# design.net
KiCad netlist of a schematic drawn in Altium Designer
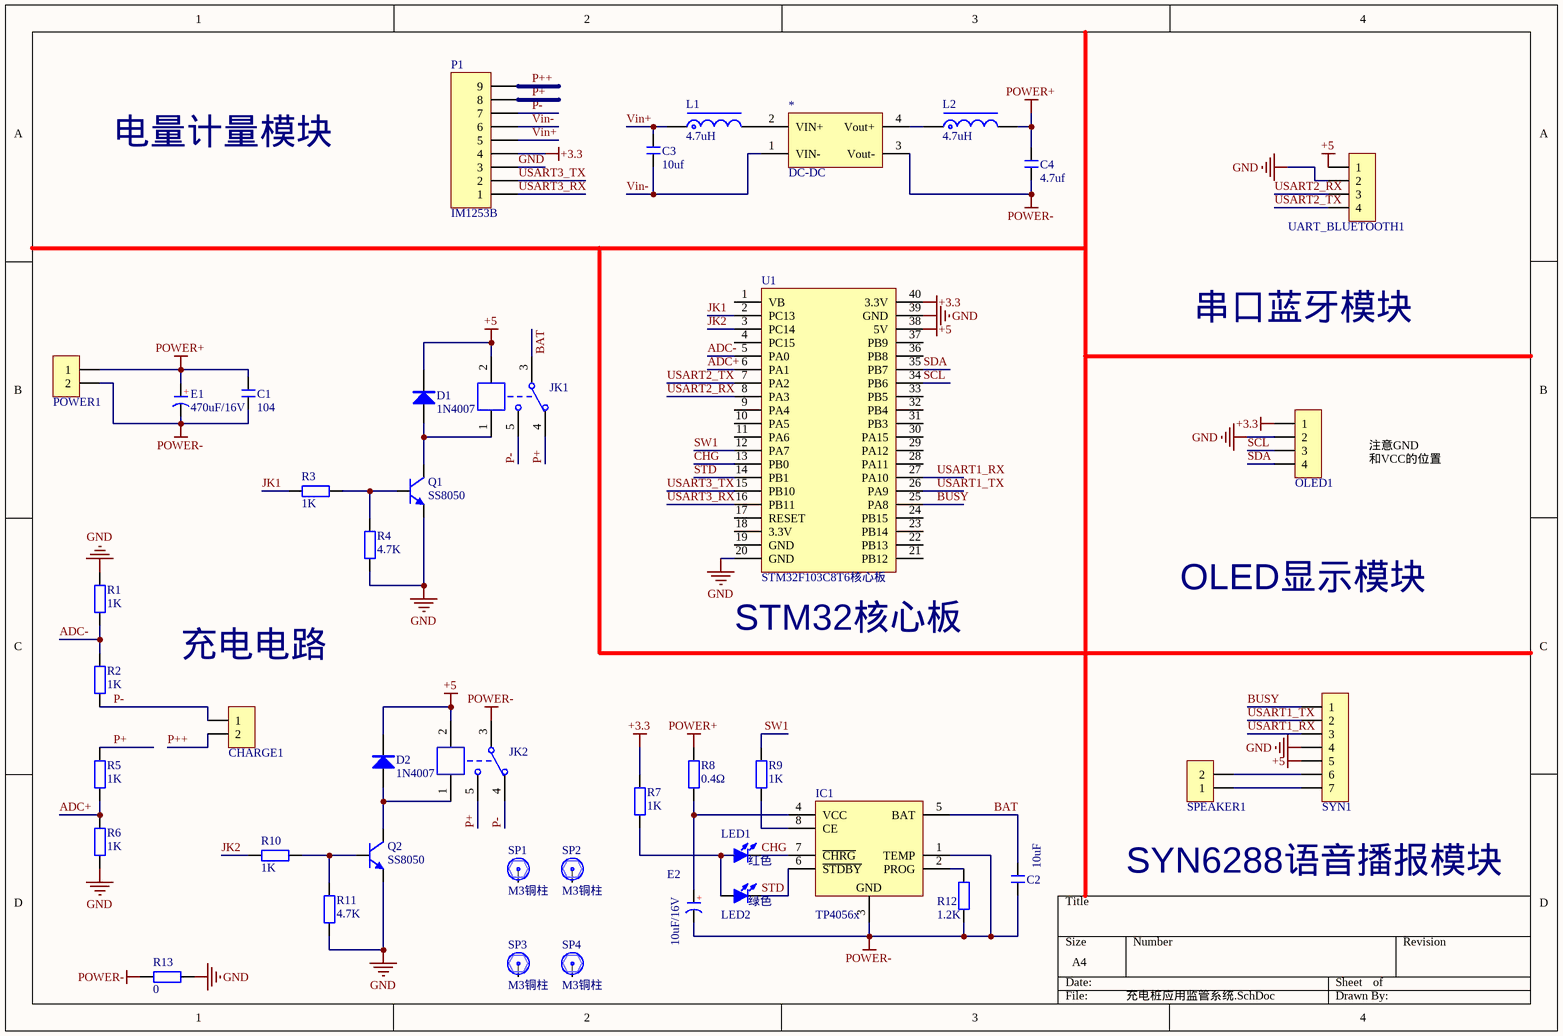
[diagram p0: 充电桩应用监管系统.SchDoc]

(export (version "E")
  (design (tool "Eeschema 10.0.6"))
  (components
    (comp (ref "*") (value "DC-DC") (libsource (lib "HLK-1D0505A") (part "Component_1")))
    (comp (ref "C1")
      (value "104")
      (footprint "R 0805_M")
      (description "直插瓷片电容")
      (fields (field (name "版权归属") "源创客"))
      (libsource (lib "3.1   - 电阻-电容-电感") (part "C-CC"))
    )
    (comp (ref "C2")
      (value "10uF")
      (footprint "C 1206_M")
      (description "无极性贴片电容")
      (fields (field (name "版权归属") "源创客"))
      (libsource (lib "3.1   - 电阻-电容-电感") (part "C"))
    )
    (comp (ref "C3")
      (value "10uf")
      (footprint "R 0805_M")
      (description "直插瓷片电容")
      (fields (field (name "版权归属") "源创客"))
      (libsource (lib "3.1   - 电阻-电容-电感") (part "C-CC"))
    )
    (comp (ref "C4")
      (value "4.7uf")
      (footprint "R 0805_M")
      (description "直插瓷片电容")
      (fields (field (name "版权归属") "源创客"))
      (libsource (lib "3.1   - 电阻-电容-电感") (part "C-CC"))
    )
    (comp (ref "CHARGE1")
      (value "HDR-1X2")
      (footprint "KF301-5.0-2P")
      (description "2P接插件")
      (fields (field (name "版权归属") "源创客"))
      (libsource (lib "") (part "Header 2_2"))
    )
    (comp (ref "D1")
      (value "1N4007")
      (footprint "DO-41")
      (description "整流二极管")
      (fields (field (name "版权归属") "源创客"))
      (libsource (lib "8.1   - 二极管-整流桥") (part "1N4007"))
    )
    (comp (ref "D2")
      (value "1N4007")
      (footprint "DO-41")
      (description "整流二极管")
      (fields (field (name "版权归属") "源创客"))
      (libsource (lib "8.1   - 二极管-整流桥") (part "1N4007"))
    )
    (comp (ref "E1")
      (value "470uF/16V")
      (footprint "CAP 2.0*5*11 - BK")
      (description "直插电解电容")
      (fields (field (name "版权归属") "源创客"))
      (libsource (lib "3.1   - 电阻-电容-电感") (part "C-CAP"))
    )
    (comp (ref "E2")
      (value "10uF/16V")
      (footprint "CAP 2.0*5*11 - BK")
      (description "直插电解电容")
      (fields (field (name "版权归属") "源创客"))
      (libsource (lib "3.1   - 电阻-电容-电感") (part "C-CAP"))
    )
    (comp (ref "IC1")
      (value "TP4056x")
      (footprint "ESOP8_M")
      (description "锂电池充电管理")
      (fields (field (name "版权归属") "源创客"))
      (libsource (lib "1.3   - 电源类芯片") (part "TP4056"))
    )
    (comp (ref "JK1")
      (value "~")
      (footprint "SRD-C_B")
      (description "5V一组转换")
      (fields (field (name "版权归属") "源创客"))
      (libsource (lib "7.1   - 继电器") (part "SRD-05VDC-SL-C"))
    )
    (comp (ref "JK2")
      (value "~")
      (footprint "SRD-C_B")
      (description "5V一组转换")
      (fields (field (name "版权归属") "源创客"))
      (libsource (lib "7.1   - 继电器") (part "SRD-05VDC-SL-C"))
    )
    (comp (ref "L1")
      (value "4.7uH")
      (footprint "NR2520")
      (description "NR磁胶电感")
      (fields (field (name "版权归属") "源创客"))
      (libsource (lib "3.1   - 电阻-电容-电感") (part "L-NR"))
    )
    (comp (ref "L2")
      (value "4.7uH")
      (footprint "NR2520")
      (description "NR磁胶电感")
      (fields (field (name "版权归属") "源创客"))
      (libsource (lib "3.1   - 电阻-电容-电感") (part "L-NR"))
    )
    (comp (ref "LED1")
      (value "红色")
      (footprint "LED 0805R")
      (description "插件LED")
      (fields (field (name "版权归属") "源创客"))
      (libsource (lib "9.1   - LED") (part "LED-3MM"))
    )
    (comp (ref "LED2")
      (value "绿色")
      (footprint "LED 0805G")
      (description "插件LED")
      (fields (field (name "版权归属") "源创客"))
      (libsource (lib "9.1   - LED") (part "LED-3MM"))
    )
    (comp (ref "OLED1")
      (value "HDR-1X4")
      (footprint "HDR2.54-M-LI-4P")
      (description "4P接插件")
      (fields (field (name "版权归属") "源创客"))
      (libsource (lib "4.5   - 接插件-脚距2.54") (part "Header 4"))
    )
    (comp (ref "P1")
      (value "IM1253B")
      (footprint "HDR1X9")
      (description "Header, 9-Pin")
      (fields (field (name "PUBLISHER") "Altium Limited"))
      (libsource (lib "Miscellaneous Connectors") (part "Header 9"))
    )
    (comp (ref "POWER1")
      (value "HDR-1X2")
      (footprint "KF301-5.0-2P")
      (description "2P接插件")
      (fields (field (name "版权归属") "源创客"))
      (libsource (lib "") (part "Header 2_1"))
    )
    (comp (ref "Q1")
      (value "SS8050")
      (footprint "TO92A")
      (description "高频放大-NPN型")
      (fields (field (name "版权归属") "源创客"))
      (libsource (lib "6.2   - 三极管") (part "8050-DIP"))
    )
    (comp (ref "Q2")
      (value "SS8050")
      (footprint "TO92A")
      (description "高频放大-NPN型")
      (fields (field (name "版权归属") "源创客"))
      (libsource (lib "6.2   - 三极管") (part "8050-DIP"))
    )
    (comp (ref "R1")
      (value "1K")
      (footprint "R 0805_M")
      (description "直插色环电阻")
      (fields (field (name "版权归属") "源创客"))
      (libsource (lib "3.1   - 电阻-电容-电感") (part "R-CRR"))
    )
    (comp (ref "R2")
      (value "1K")
      (footprint "R 0805_M")
      (description "直插色环电阻")
      (fields (field (name "版权归属") "源创客"))
      (libsource (lib "3.1   - 电阻-电容-电感") (part "R-CRR"))
    )
    (comp (ref "R3")
      (value "1K")
      (footprint "R 0805_M")
      (description "直插色环电阻")
      (fields (field (name "版权归属") "源创客"))
      (libsource (lib "3.1   - 电阻-电容-电感") (part "R-CRR"))
    )
    (comp (ref "R4")
      (value "4.7K")
      (footprint "R 0805_M")
      (description "直插色环电阻")
      (fields (field (name "版权归属") "源创客"))
      (libsource (lib "3.1   - 电阻-电容-电感") (part "R-CRR"))
    )
    (comp (ref "R5")
      (value "1K")
      (footprint "R 0805_M")
      (description "直插色环电阻")
      (fields (field (name "版权归属") "源创客"))
      (libsource (lib "3.1   - 电阻-电容-电感") (part "R-CRR"))
    )
    (comp (ref "R6")
      (value "1K")
      (footprint "R 0805_M")
      (description "直插色环电阻")
      (fields (field (name "版权归属") "源创客"))
      (libsource (lib "3.1   - 电阻-电容-电感") (part "R-CRR"))
    )
    (comp (ref "R7")
      (value "1K")
      (footprint "R 0805_M")
      (description "直插色环电阻")
      (fields (field (name "版权归属") "源创客"))
      (libsource (lib "3.1   - 电阻-电容-电感") (part "R-CRR"))
    )
    (comp (ref "R8")
      (value "0.4Ω")
      (footprint "R 0805_M")
      (description "直插色环电阻")
      (fields (field (name "版权归属") "源创客"))
      (libsource (lib "3.1   - 电阻-电容-电感") (part "R-CRR"))
    )
    (comp (ref "R9")
      (value "1K")
      (footprint "R 0805_M")
      (description "直插色环电阻")
      (fields (field (name "版权归属") "源创客"))
      (libsource (lib "3.1   - 电阻-电容-电感") (part "R-CRR"))
    )
    (comp (ref "R10")
      (value "1K")
      (footprint "R 0805_M")
      (description "直插色环电阻")
      (fields (field (name "版权归属") "源创客"))
      (libsource (lib "3.1   - 电阻-电容-电感") (part "R-CRR"))
    )
    (comp (ref "R11")
      (value "4.7K")
      (footprint "R 0805_M")
      (description "直插色环电阻")
      (fields (field (name "版权归属") "源创客"))
      (libsource (lib "3.1   - 电阻-电容-电感") (part "R-CRR"))
    )
    (comp (ref "R12")
      (value "1.2K")
      (footprint "R 0805_M")
      (description "直插色环电阻")
      (fields (field (name "版权归属") "源创客"))
      (libsource (lib "3.1   - 电阻-电容-电感") (part "R-CRR"))
    )
    (comp (ref "R13")
      (value "0")
      (footprint "R 0805_M")
      (description "直插色环电阻")
      (fields (field (name "版权归属") "源创客"))
      (libsource (lib "3.1   - 电阻-电容-电感") (part "R-CRR"))
    )
    (comp (ref "SP1")
      (value "M3铜柱")
      (footprint "M3x4_L")
      (description "铜柱")
      (fields (field (name "版权归属") "源创客"))
      (libsource (lib "15.1 - 未分类器件") (part "铜柱小焊盘"))
    )
    (comp (ref "SP2")
      (value "M3铜柱")
      (footprint "M3x4_L")
      (description "铜柱")
      (fields (field (name "版权归属") "源创客"))
      (libsource (lib "15.1 - 未分类器件") (part "铜柱小焊盘"))
    )
    (comp (ref "SP3")
      (value "M3铜柱")
      (footprint "M3x4_L")
      (description "铜柱")
      (fields (field (name "版权归属") "源创客"))
      (libsource (lib "15.1 - 未分类器件") (part "铜柱小焊盘"))
    )
    (comp (ref "SP4")
      (value "M3铜柱")
      (footprint "M3x4_L")
      (description "铜柱")
      (fields (field (name "版权归属") "源创客"))
      (libsource (lib "15.1 - 未分类器件") (part "铜柱小焊盘"))
    )
    (comp (ref "SPEAKER1")
      (value "HDR-1X2")
      (footprint "KF301-5.0-2P")
      (description "2P接插件")
      (fields (field (name "版权归属") "源创客"))
      (libsource (lib "4.9   - 接插件-脚距5.0") (part "Header 2"))
    )
    (comp (ref "SYN1")
      (value "HDR-1X7")
      (footprint "PH2.0-LI-7P")
      (description "7P接插件")
      (fields (field (name "版权归属") "源创客"))
      (libsource (lib "4.4   - 接插件-脚距2.0") (part "Header 7"))
    )
    (comp (ref "U1")
      (value "STM32F103C8T6核心板")
      (footprint "DIP40-600_MH")
      (libsource (lib "STM32F103C8T6核心板") (part "STM32F103C8T6核心板"))
    )
    (comp (ref "UART_BLUETOOTH1")
      (value "HDR-1X4")
      (footprint "HDR2.54-M-LI-4P")
      (description "4P接插件")
      (fields (field (name "版权归属") "源创客"))
      (libsource (lib "4.5   - 接插件-脚距2.54") (part "Header 4"))
    )
  )
  (nets
    (net (code "1") (name "+3.3") (class "Default")
      (node (ref "OLED1") (pin "1") (pinfunction "1_1") (pintype "passive"))
      (node (ref "P1") (pin "4") (pinfunction "4_4") (pintype "passive"))
      (node (ref "R7") (pin "2") (pinfunction "2_2") (pintype "passive"))
      (node (ref "U1") (pin "40") (pinfunction "3.3V_40") (pintype "passive"))
    )
    (net (code "2") (name "+5") (class "Default")
      (node (ref "D1") (pin "2") (pinfunction "K_2") (pintype "passive"))
      (node (ref "D2") (pin "2") (pinfunction "K_2") (pintype "passive"))
      (node (ref "JK1") (pin "2") (pinfunction "2_2") (pintype "passive"))
      (node (ref "JK2") (pin "2") (pinfunction "2_2") (pintype "passive"))
      (node (ref "SYN1") (pin "5") (pinfunction "5_5") (pintype "passive"))
      (node (ref "U1") (pin "38") (pinfunction "5V_38") (pintype "passive"))
      (node (ref "UART_BLUETOOTH1") (pin "1") (pinfunction "1_1") (pintype "passive"))
    )
    (net (code "3") (name "/ADC+") (class "Default")
      (node (ref "R5") (pin "1") (pinfunction "1_1") (pintype "passive"))
      (node (ref "R6") (pin "2") (pinfunction "2_2") (pintype "passive"))
      (node (ref "U1") (pin "6") (pinfunction "PA1_6") (pintype "passive"))
    )
    (net (code "4") (name "/ADC-") (class "Default")
      (node (ref "R1") (pin "1") (pinfunction "1_1") (pintype "passive"))
      (node (ref "R2") (pin "2") (pinfunction "2_2") (pintype "passive"))
      (node (ref "U1") (pin "5") (pinfunction "PA0_5") (pintype "passive"))
    )
    (net (code "5") (name "/BAT") (class "Default")
      (node (ref "C2") (pin "2") (pinfunction "2_2") (pintype "passive"))
      (node (ref "IC1") (pin "5") (pinfunction "BAT_5") (pintype "passive"))
      (node (ref "JK1") (pin "3") (pinfunction "3_3") (pintype "passive"))
    )
    (net (code "6") (name "/BUSY") (class "Default")
      (node (ref "SYN1") (pin "1") (pinfunction "1_1") (pintype "passive"))
      (node (ref "U1") (pin "25") (pinfunction "PA8_25") (pintype "passive"))
    )
    (net (code "7") (name "/CHG") (class "Default")
      (node (ref "IC1") (pin "7") (pinfunction "~{CHRG}_7") (pintype "passive"))
      (node (ref "LED1") (pin "2") (pinfunction "K_2") (pintype "passive"))
      (node (ref "U1") (pin "13") (pinfunction "PB0_13") (pintype "passive"))
    )
    (net (code "8") (name "/JK1") (class "Default")
      (node (ref "R3") (pin "1") (pinfunction "1_1") (pintype "passive"))
      (node (ref "U1") (pin "2") (pinfunction "PC13_2") (pintype "passive"))
    )
    (net (code "9") (name "/JK2") (class "Default")
      (node (ref "R10") (pin "1") (pinfunction "1_1") (pintype "passive"))
      (node (ref "U1") (pin "3") (pinfunction "PC14_3") (pintype "passive"))
    )
    (net (code "10") (name "/P+") (class "Default")
      (node (ref "JK1") (pin "4") (pinfunction "4_4") (pintype "passive"))
      (node (ref "JK2") (pin "5") (pinfunction "5_5") (pintype "passive"))
      (node (ref "P1") (pin "8") (pinfunction "8_8") (pintype "passive"))
      (node (ref "R5") (pin "2") (pinfunction "2_2") (pintype "passive"))
    )
    (net (code "11") (name "/P++") (class "Default")
      (node (ref "CHARGE1") (pin "2") (pinfunction "2_2") (pintype "passive"))
      (node (ref "P1") (pin "9") (pinfunction "9_9") (pintype "passive"))
    )
    (net (code "12") (name "/P-") (class "Default")
      (node (ref "CHARGE1") (pin "1") (pinfunction "1_1") (pintype "passive"))
      (node (ref "JK1") (pin "5") (pinfunction "5_5") (pintype "passive"))
      (node (ref "JK2") (pin "4") (pinfunction "4_4") (pintype "passive"))
      (node (ref "P1") (pin "7") (pinfunction "7_7") (pintype "passive"))
      (node (ref "R2") (pin "1") (pinfunction "1_1") (pintype "passive"))
    )
    (net (code "13") (name "/SCL") (class "Default")
      (node (ref "OLED1") (pin "3") (pinfunction "3_3") (pintype "passive"))
      (node (ref "U1") (pin "34") (pinfunction "PB6_34") (pintype "passive"))
    )
    (net (code "14") (name "/SDA") (class "Default")
      (node (ref "OLED1") (pin "4") (pinfunction "4_4") (pintype "passive"))
      (node (ref "U1") (pin "35") (pinfunction "PB7_35") (pintype "passive"))
    )
    (net (code "15") (name "/STD") (class "Default")
      (node (ref "IC1") (pin "6") (pinfunction "~{STDBY}_6") (pintype "passive"))
      (node (ref "LED2") (pin "2") (pinfunction "K_2") (pintype "passive"))
      (node (ref "U1") (pin "14") (pinfunction "PB1_14") (pintype "passive"))
    )
    (net (code "16") (name "/SW1") (class "Default")
      (node (ref "R9") (pin "1") (pinfunction "1_1") (pintype "passive"))
      (node (ref "U1") (pin "12") (pinfunction "PA7_12") (pintype "passive"))
    )
    (net (code "17") (name "/USART1_RX") (class "Default")
      (node (ref "SYN1") (pin "3") (pinfunction "3_3") (pintype "passive"))
      (node (ref "U1") (pin "27") (pinfunction "PA10_27") (pintype "passive"))
    )
    (net (code "18") (name "/USART1_TX") (class "Default")
      (node (ref "SYN1") (pin "2") (pinfunction "2_2") (pintype "passive"))
      (node (ref "U1") (pin "26") (pinfunction "PA9_26") (pintype "passive"))
    )
    (net (code "19") (name "/USART2_RX") (class "Default")
      (node (ref "U1") (pin "8") (pinfunction "PA3_8") (pintype "passive"))
      (node (ref "UART_BLUETOOTH1") (pin "3") (pinfunction "3_3") (pintype "passive"))
    )
    (net (code "20") (name "/USART2_TX") (class "Default")
      (node (ref "U1") (pin "7") (pinfunction "PA2_7") (pintype "passive"))
      (node (ref "UART_BLUETOOTH1") (pin "4") (pinfunction "4_4") (pintype "passive"))
    )
    (net (code "21") (name "/USART3_RX") (class "Default")
      (node (ref "P1") (pin "1") (pinfunction "1_1") (pintype "passive"))
      (node (ref "U1") (pin "16") (pinfunction "PB11_16") (pintype "passive"))
    )
    (net (code "22") (name "/USART3_TX") (class "Default")
      (node (ref "P1") (pin "2") (pinfunction "2_2") (pintype "passive"))
      (node (ref "U1") (pin "15") (pinfunction "PB10_15") (pintype "passive"))
    )
    (net (code "23") (name "/Vin+") (class "Default")
      (node (ref "C3") (pin "1") (pinfunction "1_1") (pintype "passive"))
      (node (ref "L1") (pin "1") (pinfunction "1_1") (pintype "passive"))
      (node (ref "P1") (pin "5") (pinfunction "5_5") (pintype "passive"))
    )
    (net (code "24") (name "/Vin-") (class "Default")
      (node (ref "*") (pin "1") (pinfunction "VIN-_1") (pintype "passive"))
      (node (ref "C3") (pin "2") (pinfunction "2_2") (pintype "passive"))
      (node (ref "P1") (pin "6") (pinfunction "6_6") (pintype "passive"))
    )
    (net (code "25") (name "GND") (class "Default")
      (node (ref "OLED1") (pin "2") (pinfunction "2_2") (pintype "passive"))
      (node (ref "P1") (pin "3") (pinfunction "3_3") (pintype "passive"))
      (node (ref "Q1") (pin "1") (pinfunction "E_1") (pintype "passive"))
      (node (ref "Q2") (pin "1") (pinfunction "E_1") (pintype "passive"))
      (node (ref "R1") (pin "2") (pinfunction "2_2") (pintype "passive"))
      (node (ref "R11") (pin "1") (pinfunction "1_1") (pintype "passive"))
      (node (ref "R13") (pin "1") (pinfunction "1_1") (pintype "passive"))
      (node (ref "R4") (pin "1") (pinfunction "1_1") (pintype "passive"))
      (node (ref "R6") (pin "1") (pinfunction "1_1") (pintype "passive"))
      (node (ref "SYN1") (pin "4") (pinfunction "4_4") (pintype "passive"))
      (node (ref "U1") (pin "20") (pinfunction "GND_20") (pintype "passive"))
      (node (ref "U1") (pin "39") (pinfunction "GND_39") (pintype "passive"))
      (node (ref "UART_BLUETOOTH1") (pin "2") (pinfunction "2_2") (pintype "passive"))
    )
    (net (code "26") (name "Net-(*-VIN+)") (class "Default")
      (node (ref "*") (pin "2") (pinfunction "VIN+_2") (pintype "passive"))
      (node (ref "L1") (pin "2") (pinfunction "2_2") (pintype "passive"))
    )
    (net (code "27") (name "Net-(*-Vout+)") (class "Default")
      (node (ref "*") (pin "4") (pinfunction "Vout+_4") (pintype "passive"))
      (node (ref "L2") (pin "1") (pinfunction "1_1") (pintype "passive"))
    )
    (net (code "28") (name "Net-(D1-A)") (class "Default")
      (node (ref "D1") (pin "1") (pinfunction "A_1") (pintype "passive"))
      (node (ref "JK1") (pin "1") (pinfunction "1_1") (pintype "passive"))
      (node (ref "Q1") (pin "3") (pinfunction "C_3") (pintype "passive"))
    )
    (net (code "29") (name "Net-(D2-A)") (class "Default")
      (node (ref "D2") (pin "1") (pinfunction "A_1") (pintype "passive"))
      (node (ref "JK2") (pin "1") (pinfunction "1_1") (pintype "passive"))
      (node (ref "Q2") (pin "3") (pinfunction "C_3") (pintype "passive"))
    )
    (net (code "30") (name "Net-(E2-A)") (class "Default")
      (node (ref "E2") (pin "1") (pinfunction "A_1") (pintype "passive"))
      (node (ref "IC1") (pin "4") (pinfunction "VCC_4") (pintype "passive"))
      (node (ref "R8") (pin "1") (pinfunction "1_1") (pintype "passive"))
    )
    (net (code "31") (name "Net-(IC1-CE)") (class "Default")
      (node (ref "IC1") (pin "8") (pinfunction "CE_8") (pintype "passive"))
      (node (ref "R9") (pin "2") (pinfunction "2_2") (pintype "passive"))
    )
    (net (code "32") (name "Net-(IC1-PROG)") (class "Default")
      (node (ref "IC1") (pin "2") (pinfunction "PROG_2") (pintype "passive"))
      (node (ref "R12") (pin "2") (pinfunction "2_2") (pintype "passive"))
    )
    (net (code "33") (name "Net-(LED1-A)") (class "Default")
      (node (ref "LED1") (pin "1") (pinfunction "A_1") (pintype "passive"))
      (node (ref "LED2") (pin "1") (pinfunction "A_1") (pintype "passive"))
      (node (ref "R7") (pin "1") (pinfunction "1_1") (pintype "passive"))
    )
    (net (code "34") (name "Net-(Q1-B)") (class "Default")
      (node (ref "Q1") (pin "2") (pinfunction "B_2") (pintype "passive"))
      (node (ref "R3") (pin "2") (pinfunction "2_2") (pintype "passive"))
      (node (ref "R4") (pin "2") (pinfunction "2_2") (pintype "passive"))
    )
    (net (code "35") (name "Net-(Q2-B)") (class "Default")
      (node (ref "Q2") (pin "2") (pinfunction "B_2") (pintype "passive"))
      (node (ref "R10") (pin "2") (pinfunction "2_2") (pintype "passive"))
      (node (ref "R11") (pin "2") (pinfunction "2_2") (pintype "passive"))
    )
    (net (code "36") (name "Net-(SPEAKER1-Pad1)") (class "Default")
      (node (ref "SPEAKER1") (pin "1") (pinfunction "1_1") (pintype "passive"))
      (node (ref "SYN1") (pin "7") (pinfunction "7_7") (pintype "passive"))
    )
    (net (code "37") (name "Net-(SPEAKER1-Pad2)") (class "Default")
      (node (ref "SPEAKER1") (pin "2") (pinfunction "2_2") (pintype "passive"))
      (node (ref "SYN1") (pin "6") (pinfunction "6_6") (pintype "passive"))
    )
    (net (code "38") (name "POWER+") (class "Default")
      (node (ref "C1") (pin "1") (pinfunction "1_1") (pintype "passive"))
      (node (ref "C4") (pin "1") (pinfunction "1_1") (pintype "passive"))
      (node (ref "E1") (pin "1") (pinfunction "A_1") (pintype "passive"))
      (node (ref "L2") (pin "2") (pinfunction "2_2") (pintype "passive"))
      (node (ref "POWER1") (pin "1") (pinfunction "1_1") (pintype "passive"))
      (node (ref "R8") (pin "2") (pinfunction "2_2") (pintype "passive"))
    )
    (net (code "39") (name "POWER-") (class "Default")
      (node (ref "*") (pin "3") (pinfunction "Vout-_3") (pintype "passive"))
      (node (ref "C1") (pin "2") (pinfunction "2_2") (pintype "passive"))
      (node (ref "C2") (pin "1") (pinfunction "1_1") (pintype "passive"))
      (node (ref "C4") (pin "2") (pinfunction "2_2") (pintype "passive"))
      (node (ref "E1") (pin "2") (pinfunction "K_2") (pintype "passive"))
      (node (ref "E2") (pin "2") (pinfunction "K_2") (pintype "passive"))
      (node (ref "IC1") (pin "1") (pinfunction "TEMP_1") (pintype "passive"))
      (node (ref "IC1") (pin "3") (pinfunction "GND_3") (pintype "passive"))
      (node (ref "JK2") (pin "3") (pinfunction "3_3") (pintype "passive"))
      (node (ref "POWER1") (pin "2") (pinfunction "2_2") (pintype "passive"))
      (node (ref "R12") (pin "1") (pinfunction "1_1") (pintype "passive"))
      (node (ref "R13") (pin "2") (pinfunction "2_2") (pintype "passive"))
    )
    (net (code "40") (name "unconnected-(SP1-Pad1)") (class "Default")
      (node (ref "SP1") (pin "1") (pinfunction "1_1") (pintype "passive"))
    )
    (net (code "41") (name "unconnected-(SP2-Pad1)") (class "Default")
      (node (ref "SP2") (pin "1") (pinfunction "1_1") (pintype "passive"))
    )
    (net (code "42") (name "unconnected-(SP3-Pad1)") (class "Default")
      (node (ref "SP3") (pin "1") (pinfunction "1_1") (pintype "passive"))
    )
    (net (code "43") (name "unconnected-(SP4-Pad1)") (class "Default")
      (node (ref "SP4") (pin "1") (pinfunction "1_1") (pintype "passive"))
    )
    (net (code "44") (name "unconnected-(U1-3.3V-Pad18)") (class "Default")
      (node (ref "U1") (pin "18") (pinfunction "3.3V_18") (pintype "passive"))
    )
    (net (code "45") (name "unconnected-(U1-GND-Pad19)") (class "Default")
      (node (ref "U1") (pin "19") (pinfunction "GND_19") (pintype "passive"))
    )
    (net (code "46") (name "unconnected-(U1-PA4-Pad9)") (class "Default")
      (node (ref "U1") (pin "9") (pinfunction "PA4_9") (pintype "passive"))
    )
    (net (code "47") (name "unconnected-(U1-PA5-Pad10)") (class "Default")
      (node (ref "U1") (pin "10") (pinfunction "PA5_10") (pintype "passive"))
    )
    (net (code "48") (name "unconnected-(U1-PA6-Pad11)") (class "Default")
      (node (ref "U1") (pin "11") (pinfunction "PA6_11") (pintype "passive"))
    )
    (net (code "49") (name "unconnected-(U1-PA11-Pad28)") (class "Default")
      (node (ref "U1") (pin "28") (pinfunction "PA11_28") (pintype "passive"))
    )
    (net (code "50") (name "unconnected-(U1-PA12-Pad29)") (class "Default")
      (node (ref "U1") (pin "29") (pinfunction "PA12_29") (pintype "passive"))
    )
    (net (code "51") (name "unconnected-(U1-PA15-Pad30)") (class "Default")
      (node (ref "U1") (pin "30") (pinfunction "PA15_30") (pintype "passive"))
    )
    (net (code "52") (name "unconnected-(U1-PB3-Pad31)") (class "Default")
      (node (ref "U1") (pin "31") (pinfunction "PB3_31") (pintype "passive"))
    )
    (net (code "53") (name "unconnected-(U1-PB4-Pad32)") (class "Default")
      (node (ref "U1") (pin "32") (pinfunction "PB4_32") (pintype "passive"))
    )
    (net (code "54") (name "unconnected-(U1-PB5-Pad33)") (class "Default")
      (node (ref "U1") (pin "33") (pinfunction "PB5_33") (pintype "passive"))
    )
    (net (code "55") (name "unconnected-(U1-PB8-Pad36)") (class "Default")
      (node (ref "U1") (pin "36") (pinfunction "PB8_36") (pintype "passive"))
    )
    (net (code "56") (name "unconnected-(U1-PB9-Pad37)") (class "Default")
      (node (ref "U1") (pin "37") (pinfunction "PB9_37") (pintype "passive"))
    )
    (net (code "57") (name "unconnected-(U1-PB12-Pad21)") (class "Default")
      (node (ref "U1") (pin "21") (pinfunction "PB12_21") (pintype "passive"))
    )
    (net (code "58") (name "unconnected-(U1-PB13-Pad22)") (class "Default")
      (node (ref "U1") (pin "22") (pinfunction "PB13_22") (pintype "passive"))
    )
    (net (code "59") (name "unconnected-(U1-PB14-Pad23)") (class "Default")
      (node (ref "U1") (pin "23") (pinfunction "PB14_23") (pintype "passive"))
    )
    (net (code "60") (name "unconnected-(U1-PB15-Pad24)") (class "Default")
      (node (ref "U1") (pin "24") (pinfunction "PB15_24") (pintype "passive"))
    )
    (net (code "61") (name "unconnected-(U1-PC15-Pad4)") (class "Default")
      (node (ref "U1") (pin "4") (pinfunction "PC15_4") (pintype "passive"))
    )
    (net (code "62") (name "unconnected-(U1-RESET-Pad17)") (class "Default")
      (node (ref "U1") (pin "17") (pinfunction "RESET_17") (pintype "passive"))
    )
    (net (code "63") (name "unconnected-(U1-VB-Pad1)") (class "Default")
      (node (ref "U1") (pin "1") (pinfunction "VB_1") (pintype "passive"))
    )
  )
)
